# AOA-control-revD_SMD-sink.net
KiCad netlist of a schematic drawn in EAGLE
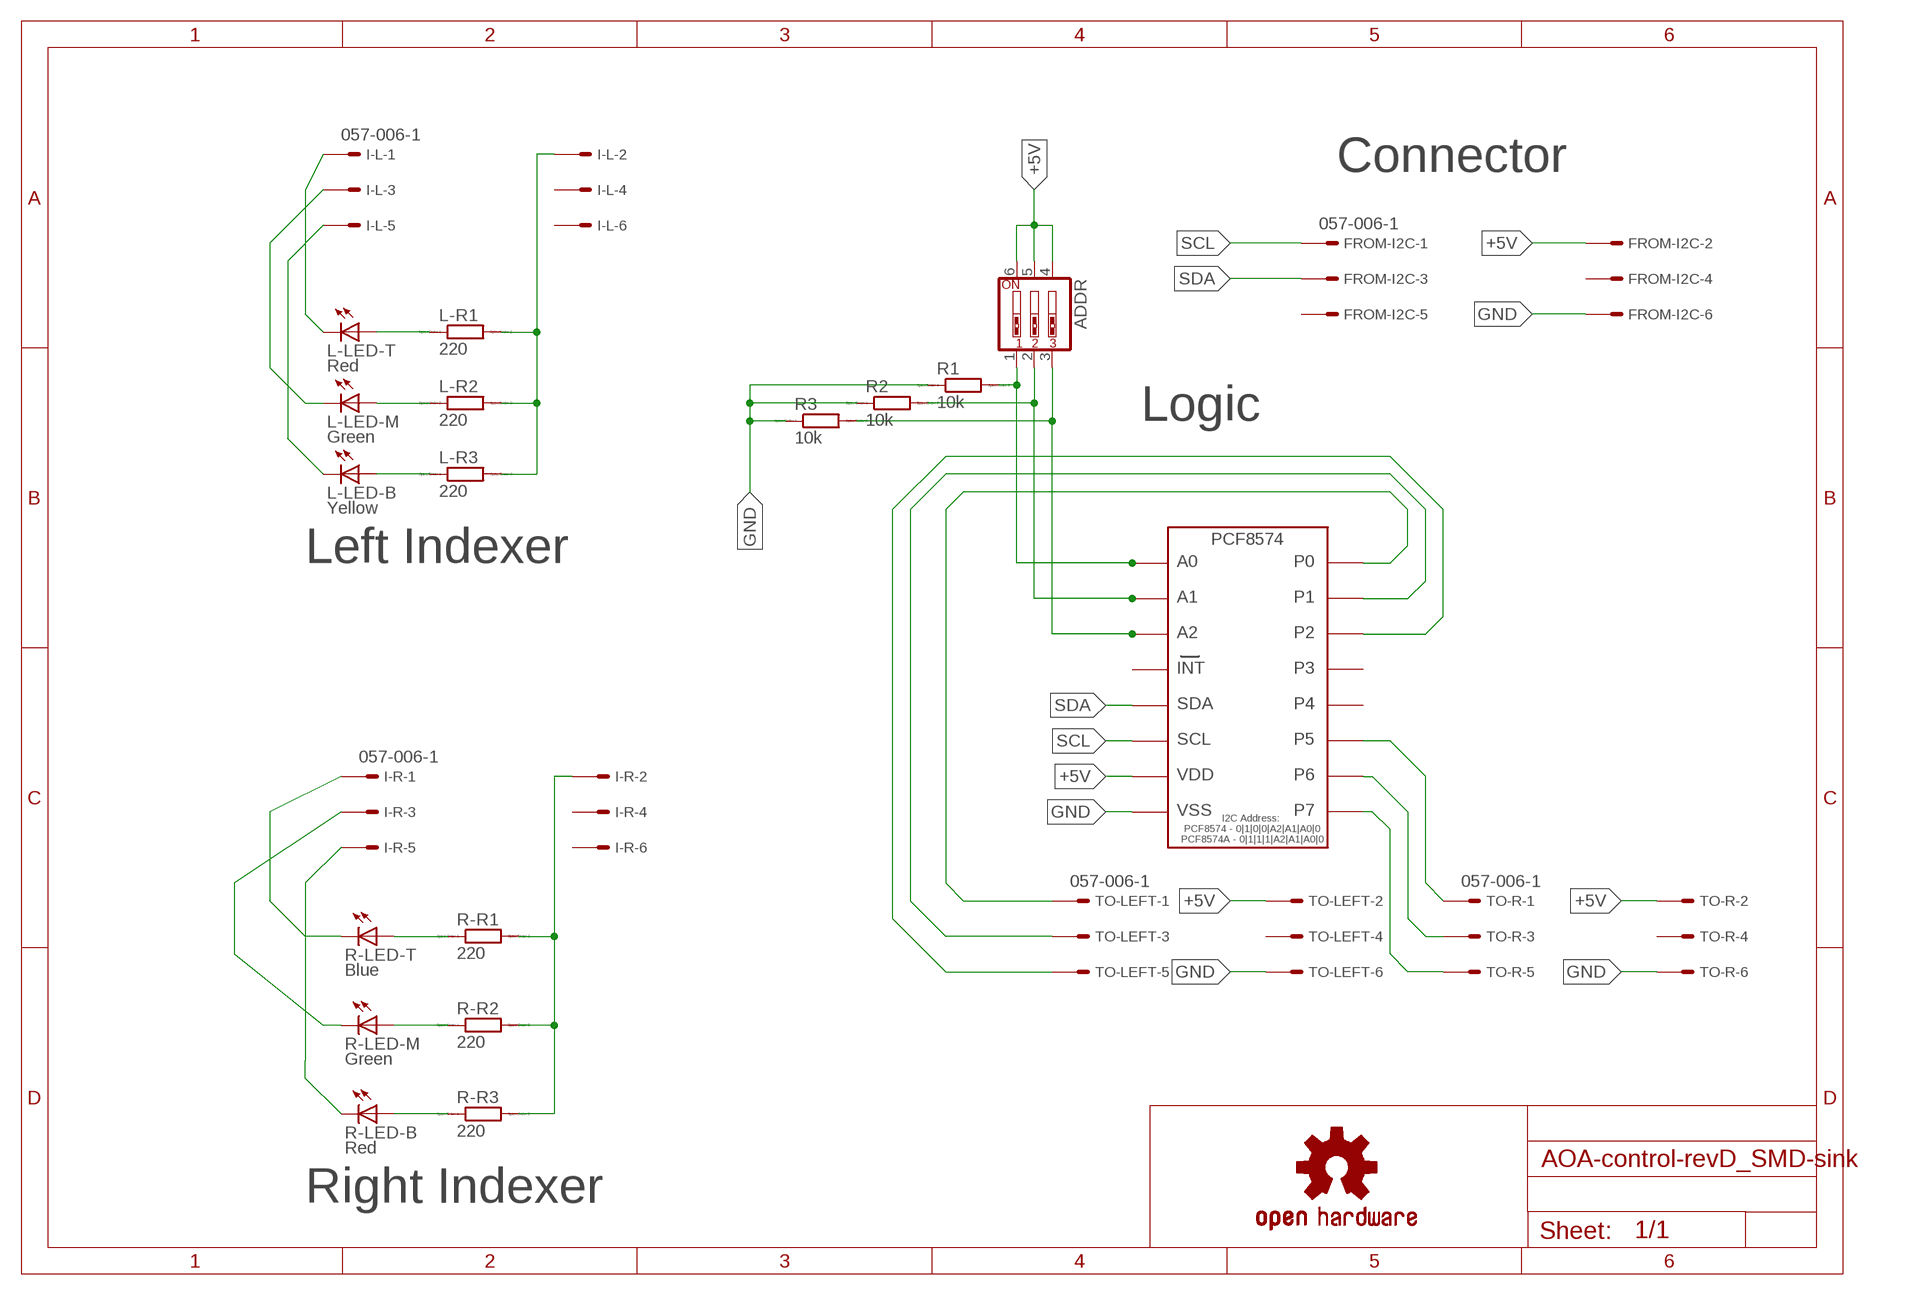
[diagram p0: schematic, sheet 1]

(export (version "E")
  (design (tool "Eeschema 10.0.6"))
  (components
    (comp (ref "ADDR")
      (value "SW_DIP-3")
      (footprint "eagle-import:EDG-03")
      (libsource (lib "eagle-import") (part "SW_DIP-3"))
    )
    (comp (ref "FROM-I2C")
      (value "057-006-1")
      (footprint "eagle-import:057-006-1")
      (libsource (lib "eagle-import") (part "057-006-1"))
    )
    (comp (ref "I-L")
      (value "057-006-1")
      (footprint "eagle-import:057-006-1")
      (libsource (lib "eagle-import") (part "057-006-1"))
    )
    (comp (ref "I-R")
      (value "057-006-1")
      (footprint "eagle-import:057-006-1")
      (libsource (lib "eagle-import") (part "057-006-1"))
    )
    (comp (ref "L-LED-B")
      (value "Yellow")
      (footprint "eagle-import:CP41B")
      (libsource (lib "eagle-import") (part "LED-2AC-CP41B-WGS"))
    )
    (comp (ref "L-LED-M")
      (value "Green")
      (footprint "eagle-import:CP41B")
      (libsource (lib "eagle-import") (part "LED-2AC-CP41B-WGS"))
    )
    (comp (ref "L-LED-T")
      (value "Red")
      (footprint "eagle-import:CP41B")
      (libsource (lib "eagle-import") (part "LED-2AC-CP41B-WGS"))
    )
    (comp (ref "L-R1")
      (value "220")
      (footprint "eagle-import:R0805")
      (libsource (lib "eagle-import") (part "R-EU_R0805"))
    )
    (comp (ref "L-R2")
      (value "220")
      (footprint "eagle-import:R0805")
      (libsource (lib "eagle-import") (part "R-EU_R0805"))
    )
    (comp (ref "L-R3")
      (value "220")
      (footprint "eagle-import:R0805")
      (libsource (lib "eagle-import") (part "R-EU_R0805"))
    )
    (comp (ref "LOGO1")
      (value "OSHW-LOGOS")
      (footprint "eagle-import:OSHW-LOGO-S")
      (libsource (lib "eagle-import") (part "OSHW-LOGOS"))
    )
    (comp (ref "R-LED-B")
      (value "Red")
      (footprint "eagle-import:CP41B")
      (libsource (lib "eagle-import") (part "LED-2AC-CP41B-WGS"))
    )
    (comp (ref "R-LED-M")
      (value "Green")
      (footprint "eagle-import:CP41B")
      (libsource (lib "eagle-import") (part "LED-2AC-CP41B-WGS"))
    )
    (comp (ref "R-LED-T")
      (value "Blue")
      (footprint "eagle-import:CP41B")
      (libsource (lib "eagle-import") (part "LED-2AC-CP41B-WGS"))
    )
    (comp (ref "R-R1")
      (value "220")
      (footprint "eagle-import:R0805")
      (libsource (lib "eagle-import") (part "R-EU_R0805"))
    )
    (comp (ref "R-R2")
      (value "220")
      (footprint "eagle-import:R0805")
      (libsource (lib "eagle-import") (part "R-EU_R0805"))
    )
    (comp (ref "R-R3")
      (value "220")
      (footprint "eagle-import:R0805")
      (libsource (lib "eagle-import") (part "R-EU_R0805"))
    )
    (comp (ref "R1")
      (value "10k")
      (footprint "eagle-import:R0805")
      (libsource (lib "eagle-import") (part "R-EU_R0805"))
    )
    (comp (ref "R2")
      (value "10k")
      (footprint "eagle-import:R0805")
      (libsource (lib "eagle-import") (part "R-EU_R0805"))
    )
    (comp (ref "R3")
      (value "10k")
      (footprint "eagle-import:R0805")
      (libsource (lib "eagle-import") (part "R-EU_R0805"))
    )
    (comp (ref "TO-LEFT")
      (value "057-006-1")
      (footprint "eagle-import:057-006-1")
      (libsource (lib "eagle-import") (part "057-006-1"))
    )
    (comp (ref "TO-R")
      (value "057-006-1")
      (footprint "eagle-import:057-006-1")
      (libsource (lib "eagle-import") (part "057-006-1"))
    )
    (comp (ref "U$1")
      (value "PCF8574P/AP")
      (footprint "eagle-import:DIP16")
      (libsource (lib "eagle-import") (part "PCF8574P/AP"))
    )
  )
  (nets
    (net (code "1") (name "+5V") (class "Default")
      (node (ref "ADDR") (pin "4") (pinfunction "4_4") (pintype "passive"))
      (node (ref "ADDR") (pin "5") (pinfunction "5_5") (pintype "passive"))
      (node (ref "ADDR") (pin "6") (pinfunction "6_6") (pintype "passive"))
      (node (ref "FROM-I2C") (pin "2") (pinfunction "S_2") (pintype "passive"))
      (node (ref "TO-LEFT") (pin "2") (pinfunction "S_2") (pintype "passive"))
      (node (ref "TO-R") (pin "2") (pinfunction "S_2") (pintype "passive"))
      (node (ref "U$1") (pin "VDD") (pinfunction "VDD_VDD") (pintype "bidirectional"))
    )
    (net (code "2") (name "GND") (class "Default")
      (node (ref "FROM-I2C") (pin "6") (pinfunction "S_6") (pintype "passive"))
      (node (ref "R1") (pin "1") (pinfunction "1_1") (pintype "passive"))
      (node (ref "R2") (pin "1") (pinfunction "1_1") (pintype "passive"))
      (node (ref "R3") (pin "1") (pinfunction "1_1") (pintype "passive"))
      (node (ref "TO-LEFT") (pin "6") (pinfunction "S_6") (pintype "passive"))
      (node (ref "TO-R") (pin "6") (pinfunction "S_6") (pintype "passive"))
      (node (ref "U$1") (pin "VSS") (pinfunction "VSS_VSS") (pintype "bidirectional"))
    )
    (net (code "3") (name "Net-(ADDR-Pad1)") (class "Default")
      (node (ref "ADDR") (pin "1") (pinfunction "1_1") (pintype "passive"))
      (node (ref "R1") (pin "2") (pinfunction "2_2") (pintype "passive"))
      (node (ref "U$1") (pin "A0") (pinfunction "A0_A0") (pintype "bidirectional"))
    )
    (net (code "4") (name "Net-(ADDR-Pad2)") (class "Default")
      (node (ref "ADDR") (pin "2") (pinfunction "2_2") (pintype "passive"))
      (node (ref "R2") (pin "2") (pinfunction "2_2") (pintype "passive"))
      (node (ref "U$1") (pin "A1") (pinfunction "A1_A1") (pintype "bidirectional"))
    )
    (net (code "5") (name "Net-(ADDR-Pad3)") (class "Default")
      (node (ref "ADDR") (pin "3") (pinfunction "3_3") (pintype "passive"))
      (node (ref "R3") (pin "2") (pinfunction "2_2") (pintype "passive"))
      (node (ref "U$1") (pin "A2") (pinfunction "A2_A2") (pintype "bidirectional"))
    )
    (net (code "6") (name "Net-(I-LA-S)") (class "Default")
      (node (ref "I-L") (pin "1") (pinfunction "S_1") (pintype "passive"))
      (node (ref "L-LED-T") (pin "1") (pinfunction "C_1") (pintype "passive"))
      (node (ref "L-LED-T") (pin "4") (pinfunction "C_4") (pintype "passive"))
    )
    (net (code "7") (name "Net-(I-LB-S)") (class "Default")
      (node (ref "I-L") (pin "2") (pinfunction "S_2") (pintype "passive"))
      (node (ref "L-R1") (pin "2") (pinfunction "2_2") (pintype "passive"))
      (node (ref "L-R2") (pin "2") (pinfunction "2_2") (pintype "passive"))
      (node (ref "L-R3") (pin "2") (pinfunction "2_2") (pintype "passive"))
    )
    (net (code "8") (name "Net-(I-LC-S)") (class "Default")
      (node (ref "I-L") (pin "3") (pinfunction "S_3") (pintype "passive"))
      (node (ref "L-LED-M") (pin "1") (pinfunction "C_1") (pintype "passive"))
      (node (ref "L-LED-M") (pin "4") (pinfunction "C_4") (pintype "passive"))
    )
    (net (code "9") (name "Net-(I-LE-S)") (class "Default")
      (node (ref "I-L") (pin "5") (pinfunction "S_5") (pintype "passive"))
      (node (ref "L-LED-B") (pin "1") (pinfunction "C_1") (pintype "passive"))
      (node (ref "L-LED-B") (pin "4") (pinfunction "C_4") (pintype "passive"))
    )
    (net (code "10") (name "Net-(I-RA-S)") (class "Default")
      (node (ref "I-R") (pin "1") (pinfunction "S_1") (pintype "passive"))
      (node (ref "R-LED-T") (pin "1") (pinfunction "C_1") (pintype "passive"))
      (node (ref "R-LED-T") (pin "4") (pinfunction "C_4") (pintype "passive"))
    )
    (net (code "11") (name "Net-(I-RB-S)") (class "Default")
      (node (ref "I-R") (pin "2") (pinfunction "S_2") (pintype "passive"))
      (node (ref "R-R1") (pin "2") (pinfunction "2_2") (pintype "passive"))
      (node (ref "R-R2") (pin "2") (pinfunction "2_2") (pintype "passive"))
      (node (ref "R-R3") (pin "2") (pinfunction "2_2") (pintype "passive"))
    )
    (net (code "12") (name "Net-(I-RC-S)") (class "Default")
      (node (ref "I-R") (pin "3") (pinfunction "S_3") (pintype "passive"))
      (node (ref "R-LED-M") (pin "1") (pinfunction "C_1") (pintype "passive"))
      (node (ref "R-LED-M") (pin "4") (pinfunction "C_4") (pintype "passive"))
    )
    (net (code "13") (name "Net-(I-RE-S)") (class "Default")
      (node (ref "I-R") (pin "5") (pinfunction "S_5") (pintype "passive"))
      (node (ref "R-LED-B") (pin "1") (pinfunction "C_1") (pintype "passive"))
      (node (ref "R-LED-B") (pin "4") (pinfunction "C_4") (pintype "passive"))
    )
    (net (code "14") (name "Net-(L-LED-B-A-Pad2)") (class "Default")
      (node (ref "L-LED-B") (pin "2") (pinfunction "A_2") (pintype "passive"))
      (node (ref "L-LED-B") (pin "3") (pinfunction "A_3") (pintype "passive"))
      (node (ref "L-R3") (pin "1") (pinfunction "1_1") (pintype "passive"))
    )
    (net (code "15") (name "Net-(L-LED-M-A-Pad2)") (class "Default")
      (node (ref "L-LED-M") (pin "2") (pinfunction "A_2") (pintype "passive"))
      (node (ref "L-LED-M") (pin "3") (pinfunction "A_3") (pintype "passive"))
      (node (ref "L-R2") (pin "1") (pinfunction "1_1") (pintype "passive"))
    )
    (net (code "16") (name "Net-(L-LED-T-A-Pad2)") (class "Default")
      (node (ref "L-LED-T") (pin "2") (pinfunction "A_2") (pintype "passive"))
      (node (ref "L-LED-T") (pin "3") (pinfunction "A_3") (pintype "passive"))
      (node (ref "L-R1") (pin "1") (pinfunction "1_1") (pintype "passive"))
    )
    (net (code "17") (name "Net-(R-LED-B-A-Pad2)") (class "Default")
      (node (ref "R-LED-B") (pin "2") (pinfunction "A_2") (pintype "passive"))
      (node (ref "R-LED-B") (pin "3") (pinfunction "A_3") (pintype "passive"))
      (node (ref "R-R3") (pin "1") (pinfunction "1_1") (pintype "passive"))
    )
    (net (code "18") (name "Net-(R-LED-M-A-Pad2)") (class "Default")
      (node (ref "R-LED-M") (pin "2") (pinfunction "A_2") (pintype "passive"))
      (node (ref "R-LED-M") (pin "3") (pinfunction "A_3") (pintype "passive"))
      (node (ref "R-R2") (pin "1") (pinfunction "1_1") (pintype "passive"))
    )
    (net (code "19") (name "Net-(R-LED-T-A-Pad2)") (class "Default")
      (node (ref "R-LED-T") (pin "2") (pinfunction "A_2") (pintype "passive"))
      (node (ref "R-LED-T") (pin "3") (pinfunction "A_3") (pintype "passive"))
      (node (ref "R-R1") (pin "1") (pinfunction "1_1") (pintype "passive"))
    )
    (net (code "20") (name "Net-(TO-LEFTA-S)") (class "Default")
      (node (ref "TO-LEFT") (pin "1") (pinfunction "S_1") (pintype "passive"))
      (node (ref "U$1") (pin "P0") (pinfunction "P0_P0") (pintype "bidirectional"))
    )
    (net (code "21") (name "Net-(TO-LEFTC-S)") (class "Default")
      (node (ref "TO-LEFT") (pin "3") (pinfunction "S_3") (pintype "passive"))
      (node (ref "U$1") (pin "P1") (pinfunction "P1_P1") (pintype "bidirectional"))
    )
    (net (code "22") (name "Net-(TO-LEFTE-S)") (class "Default")
      (node (ref "TO-LEFT") (pin "5") (pinfunction "S_5") (pintype "passive"))
      (node (ref "U$1") (pin "P2") (pinfunction "P2_P2") (pintype "bidirectional"))
    )
    (net (code "23") (name "Net-(TO-RA-S)") (class "Default")
      (node (ref "TO-R") (pin "1") (pinfunction "S_1") (pintype "passive"))
      (node (ref "U$1") (pin "P5") (pinfunction "P5_P5") (pintype "bidirectional"))
    )
    (net (code "24") (name "Net-(TO-RC-S)") (class "Default")
      (node (ref "TO-R") (pin "3") (pinfunction "S_3") (pintype "passive"))
      (node (ref "U$1") (pin "P6") (pinfunction "P6_P6") (pintype "bidirectional"))
    )
    (net (code "25") (name "Net-(TO-RE-S)") (class "Default")
      (node (ref "TO-R") (pin "5") (pinfunction "S_5") (pintype "passive"))
      (node (ref "U$1") (pin "P7") (pinfunction "P7_P7") (pintype "bidirectional"))
    )
    (net (code "26") (name "SCL") (class "Default")
      (node (ref "FROM-I2C") (pin "1") (pinfunction "S_1") (pintype "passive"))
      (node (ref "U$1") (pin "SCL") (pinfunction "SCL_SCL") (pintype "bidirectional"))
    )
    (net (code "27") (name "SDA") (class "Default")
      (node (ref "FROM-I2C") (pin "3") (pinfunction "S_3") (pintype "passive"))
      (node (ref "U$1") (pin "SDA") (pinfunction "SDA_SDA") (pintype "bidirectional"))
    )
    (net (code "28") (name "unconnected-(FROM-I2CD-S-Pad4)") (class "Default")
      (node (ref "FROM-I2C") (pin "4") (pinfunction "S_4") (pintype "passive"))
    )
    (net (code "29") (name "unconnected-(FROM-I2CE-S-Pad5)") (class "Default")
      (node (ref "FROM-I2C") (pin "5") (pinfunction "S_5") (pintype "passive"))
    )
    (net (code "30") (name "unconnected-(I-LD-S-Pad4)") (class "Default")
      (node (ref "I-L") (pin "4") (pinfunction "S_4") (pintype "passive"))
    )
    (net (code "31") (name "unconnected-(I-LF-S-Pad6)") (class "Default")
      (node (ref "I-L") (pin "6") (pinfunction "S_6") (pintype "passive"))
    )
    (net (code "32") (name "unconnected-(I-RD-S-Pad4)") (class "Default")
      (node (ref "I-R") (pin "4") (pinfunction "S_4") (pintype "passive"))
    )
    (net (code "33") (name "unconnected-(I-RF-S-Pad6)") (class "Default")
      (node (ref "I-R") (pin "6") (pinfunction "S_6") (pintype "passive"))
    )
    (net (code "34") (name "unconnected-(TO-LEFTD-S-Pad4)") (class "Default")
      (node (ref "TO-LEFT") (pin "4") (pinfunction "S_4") (pintype "passive"))
    )
    (net (code "35") (name "unconnected-(TO-RD-S-Pad4)") (class "Default")
      (node (ref "TO-R") (pin "4") (pinfunction "S_4") (pintype "passive"))
    )
    (net (code "36") (name "unconnected-(U$1-PadINT)") (class "Default")
      (node (ref "U$1") (pin "INT") (pinfunction "INT_INT") (pintype "bidirectional"))
    )
    (net (code "37") (name "unconnected-(U$1-PadP3)") (class "Default")
      (node (ref "U$1") (pin "P3") (pinfunction "P3_P3") (pintype "bidirectional"))
    )
    (net (code "38") (name "unconnected-(U$1-PadP4)") (class "Default")
      (node (ref "U$1") (pin "P4") (pinfunction "P4_P4") (pintype "bidirectional"))
    )
  )
)
